# PCBv3_2_1_Arduino.net
KiCad netlist of a schematic drawn in EAGLE
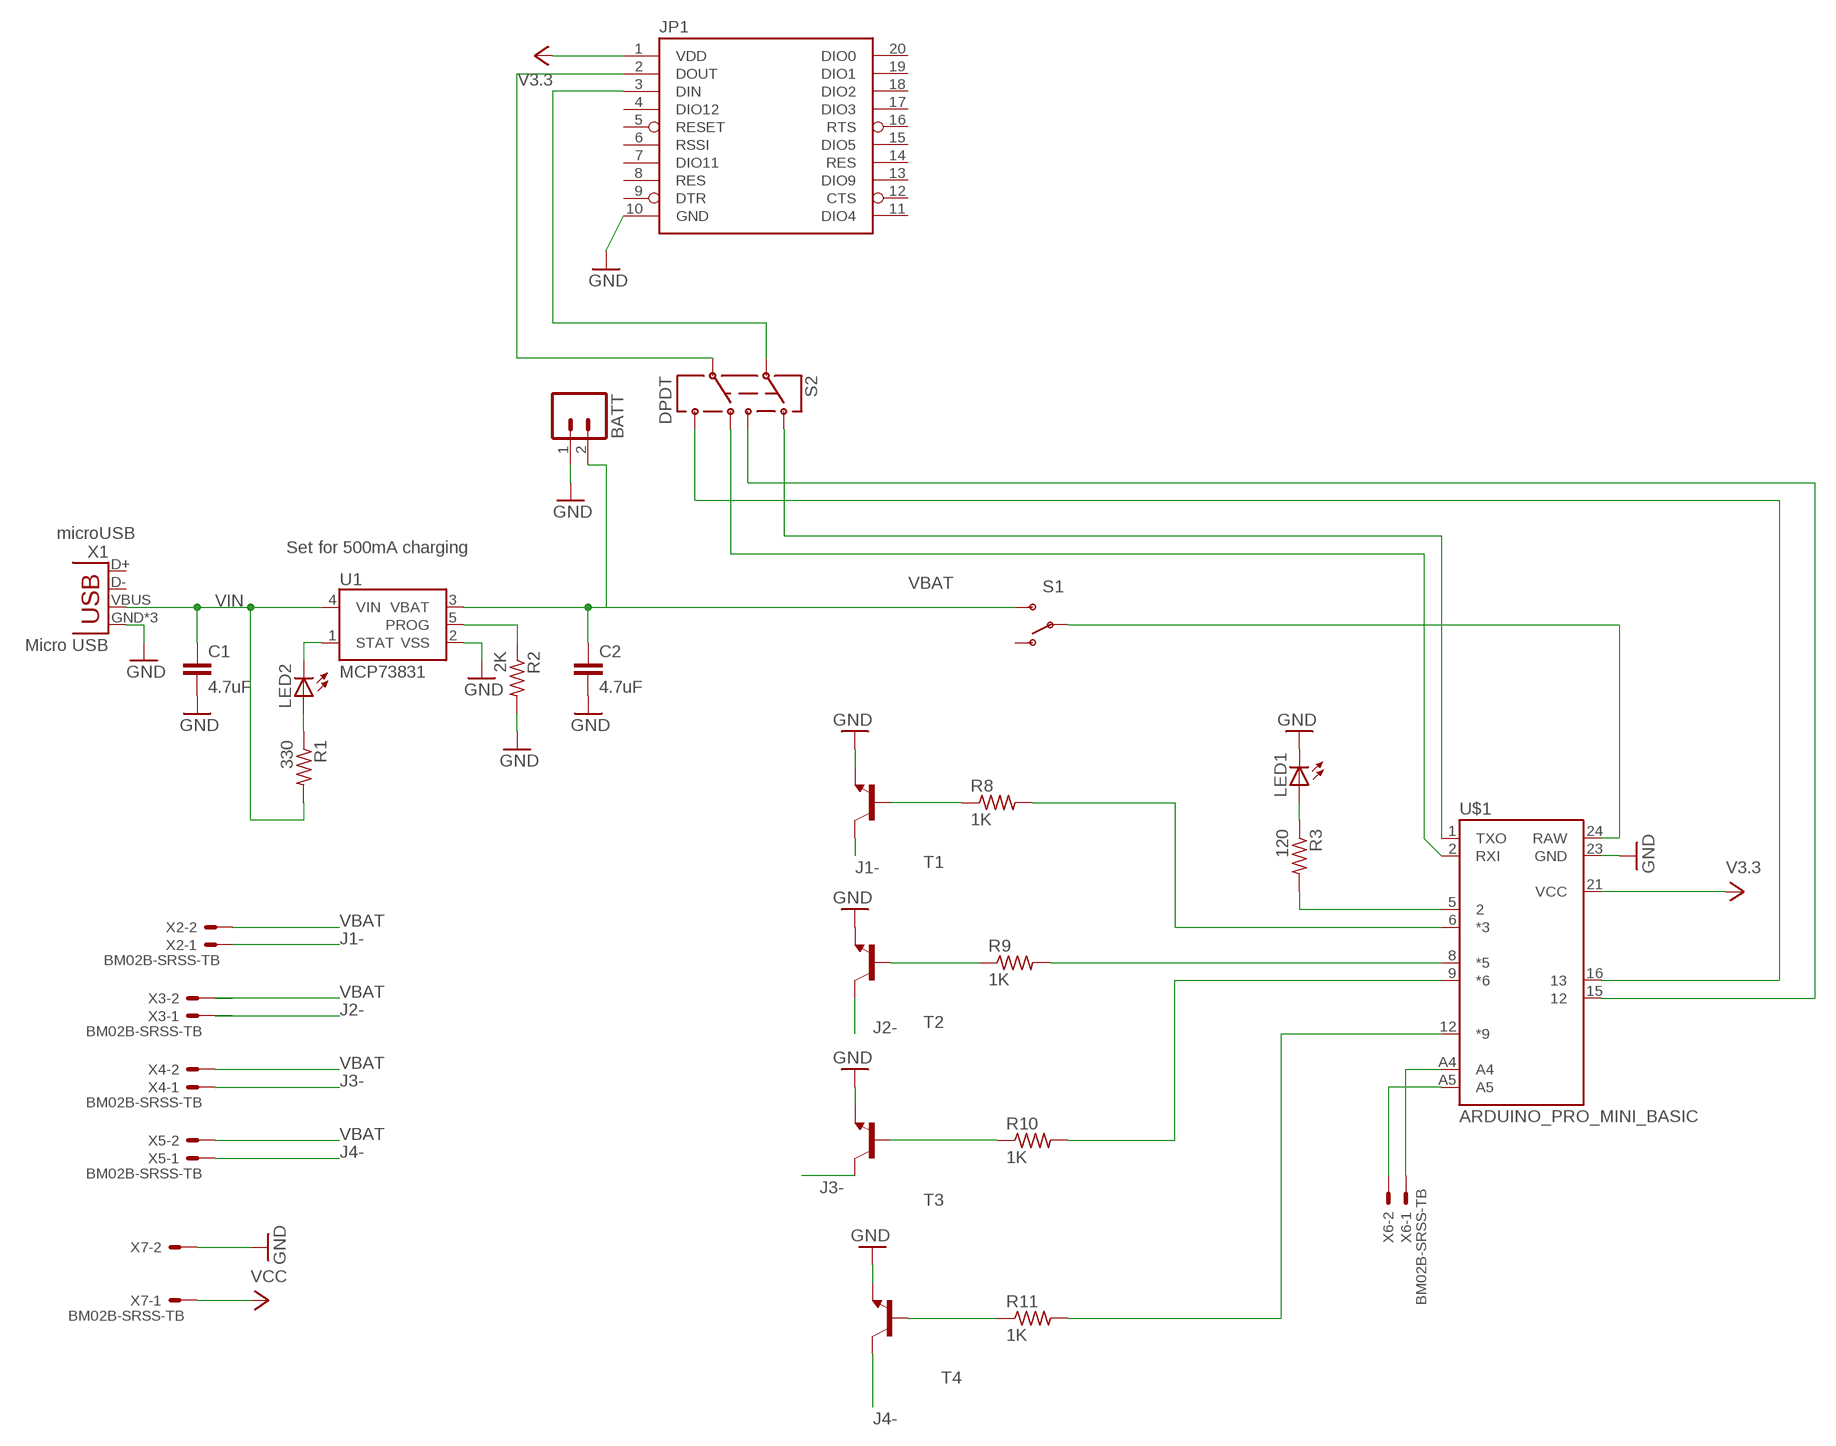
[diagram p0: schematic, sheet 1]

(export (version "E")
  (design (tool "Eeschema 10.0.6"))
  (components
    (comp (ref "BATT")
      (value "M02JST-PTH-VERT")
      (footprint "eagle-import:JST-2-PTH-VERT")
      (fields
        (field (name "MF") "JST (JAPAN SOLDERLESS TERMINALS)")
        (field (name "MPN") "S2B-PH-K-S (LF)(SN)")
      )
      (libsource (lib "eagle-import") (part "M02JST-PTH-VERT"))
    )
    (comp (ref "C1")
      (value "4.7uF")
      (footprint "eagle-import:C0805")
      (fields (field (name "MF") "TDK") (field (name "MPN") "C1005X5R0J475K050BC"))
      (libsource (lib "eagle-import") (part "C-EUC0805"))
    )
    (comp (ref "C2")
      (value "4.7uF")
      (footprint "eagle-import:C0805")
      (fields (field (name "MF") "TDK") (field (name "MPN") "C1005X5R0J475K050BC"))
      (libsource (lib "eagle-import") (part "C-EUC0805"))
    )
    (comp (ref "JP1")
      (value "XBEE-1LONGPAD")
      (footprint "eagle-import:XBEE-LONGPAD")
      (libsource (lib "eagle-import") (part "XBEE-1LONGPAD"))
    )
    (comp (ref "LED1")
      (value "LED3MM")
      (footprint "eagle-import:LED3MM")
      (fields (field (name "MF") "MULTICOMP") (field (name "MPN") "MCL034GT"))
      (libsource (lib "eagle-import") (part "LED3MM"))
    )
    (comp (ref "LED2")
      (value "LEDCHIP-LED0805")
      (footprint "eagle-import:CHIP-LED0805")
      (fields (field (name "MF") "KINGBRIGHT") (field (name "MPN") "KPT-2012QBC-D"))
      (libsource (lib "eagle-import") (part "led_LEDCHIP-LED0805"))
    )
    (comp (ref "R1")
      (value "330")
      (footprint "eagle-import:R0805")
      (fields (field (name "MF") "MULTICOMP") (field (name "MPN") "MC01W08051330R"))
      (libsource (lib "eagle-import") (part "R-US_R0805"))
    )
    (comp (ref "R2")
      (value "2K")
      (footprint "eagle-import:R0805")
      (fields (field (name "MF") "MULTICOMP") (field (name "MPN") "MC01W080512K"))
      (libsource (lib "eagle-import") (part "R-US_R0805"))
    )
    (comp (ref "R3")
      (value "120")
      (footprint "eagle-import:R0805")
      (fields (field (name "MF") "AVAGO TECHNOLOGIES") (field (name "MPN") "ASMT-YWB1-NGJB2"))
      (libsource (lib "eagle-import") (part "R-US_R0805"))
    )
    (comp (ref "R8")
      (value "1K")
      (footprint "eagle-import:R0805")
      (fields (field (name "MF") "MULTICOMP") (field (name "MPN") "MC01W08051330R"))
      (libsource (lib "eagle-import") (part "R-US_R0805"))
    )
    (comp (ref "R9")
      (value "1K")
      (footprint "eagle-import:R0805")
      (fields (field (name "MF") "MULTICOMP") (field (name "MPN") "MC01W08051330R"))
      (libsource (lib "eagle-import") (part "R-US_R0805"))
    )
    (comp (ref "R10")
      (value "1K")
      (footprint "eagle-import:R0805")
      (fields (field (name "MF") "MULTICOMP") (field (name "MPN") "MC01W08051330R"))
      (libsource (lib "eagle-import") (part "R-US_R0805"))
    )
    (comp (ref "R11")
      (value "1K")
      (footprint "eagle-import:R0805")
      (fields (field (name "MF") "MULTICOMP") (field (name "MPN") "MC01W08051330R"))
      (libsource (lib "eagle-import") (part "R-US_R0805"))
    )
    (comp (ref "S1")
      (value "SWITCH-SPDTPTH")
      (footprint "eagle-import:SWITCH-SPDT")
      (fields (field (name "MF") "EAO") (field (name "MPN") "09-10201-02"))
      (libsource (lib "eagle-import") (part "SWITCH-SPDTPTH"))
    )
    (comp (ref "S2")
      (value "DPDT")
      (footprint "eagle-import:AYZ0202")
      (fields (field (name "MF") "C & K COMPONENTS") (field (name "MPN") "AYZ0202AGRLC"))
      (libsource (lib "eagle-import") (part "AYZ0202"))
    )
    (comp (ref "T1")
      (value "BC817-16-NPN-SOT23-BEC")
      (footprint "eagle-import:SOT23-BEC")
      (fields (field (name "MF") "ON SEMICONDUCTOR") (field (name "MPN") "BC817-40LT3G"))
      (libsource (lib "eagle-import") (part "-NPN-SOT23-BECBC817-16"))
    )
    (comp (ref "T2")
      (value "BC817-16-NPN-SOT23-BEC")
      (footprint "eagle-import:SOT23-BEC")
      (fields (field (name "MF") "ON SEMICONDUCTOR") (field (name "MPN") "BC817-40LT3G"))
      (libsource (lib "eagle-import") (part "-NPN-SOT23-BECBC817-16"))
    )
    (comp (ref "T3")
      (value "BC817-16-NPN-SOT23-BEC")
      (footprint "eagle-import:SOT23-BEC")
      (fields (field (name "MF") "ON SEMICONDUCTOR") (field (name "MPN") "BC817-40LT3G"))
      (libsource (lib "eagle-import") (part "-NPN-SOT23-BECBC817-16"))
    )
    (comp (ref "T4")
      (value "BC817-16-NPN-SOT23-BEC")
      (footprint "eagle-import:SOT23-BEC")
      (fields (field (name "MF") "ON SEMICONDUCTOR") (field (name "MPN") "BC817-40LT3G"))
      (libsource (lib "eagle-import") (part "-NPN-SOT23-BECBC817-16"))
    )
    (comp (ref "U$1")
      (value "ARDUINO_PRO_MINI_BASIC")
      (footprint "eagle-import:ARDUINO_PRO_MINI_BASIC")
      (libsource (lib "eagle-import") (part "ARDUINO_PRO_MINI_BASIC"))
    )
    (comp (ref "U1")
      (value "MCP73831")
      (footprint "eagle-import:SOT23-5")
      (fields (field (name "MF") "MICROCHIP") (field (name "MPN") "MCP73831T-2ACI/OT"))
      (libsource (lib "eagle-import") (part "MCP73831"))
    )
    (comp (ref "X1")
      (value "Micro USB")
      (footprint "eagle-import:USB-MICROB")
      (fields (field (name "MF") "HIROSE(HRS)") (field (name "MPN") "ZX62-B-5PA(33)"))
      (libsource (lib "eagle-import") (part "USB-MICROB"))
    )
    (comp (ref "X2")
      (value "BM02B-SRSS-TB")
      (footprint "eagle-import:BM02B-SRSS-TB")
      (libsource (lib "eagle-import") (part "?M02B-SRSS-TBB"))
    )
    (comp (ref "X3")
      (value "BM02B-SRSS-TB")
      (footprint "eagle-import:BM02B-SRSS-TB")
      (libsource (lib "eagle-import") (part "?M02B-SRSS-TBB"))
    )
    (comp (ref "X4")
      (value "BM02B-SRSS-TB")
      (footprint "eagle-import:BM02B-SRSS-TB")
      (libsource (lib "eagle-import") (part "?M02B-SRSS-TBB"))
    )
    (comp (ref "X5")
      (value "BM02B-SRSS-TB")
      (footprint "eagle-import:BM02B-SRSS-TB")
      (libsource (lib "eagle-import") (part "?M02B-SRSS-TBB"))
    )
    (comp (ref "X6")
      (value "BM02B-SRSS-TB")
      (footprint "eagle-import:BM02B-SRSS-TB")
      (libsource (lib "eagle-import") (part "?M02B-SRSS-TBB"))
    )
    (comp (ref "X7")
      (value "BM02B-SRSS-TB")
      (footprint "eagle-import:BM02B-SRSS-TB")
      (libsource (lib "eagle-import") (part "?M02B-SRSS-TBB"))
    )
  )
  (nets
    (net (code "1") (name "/J1-") (class "Default")
      (node (ref "T1") (pin "C") (pinfunction "C_C") (pintype "passive"))
      (node (ref "X2") (pin "1") (pinfunction "S_1") (pintype "passive"))
    )
    (net (code "2") (name "/J2-") (class "Default")
      (node (ref "T2") (pin "C") (pinfunction "C_C") (pintype "passive"))
      (node (ref "X3") (pin "1") (pinfunction "S_1") (pintype "passive"))
    )
    (net (code "3") (name "/J3-") (class "Default")
      (node (ref "T3") (pin "C") (pinfunction "C_C") (pintype "passive"))
      (node (ref "X4") (pin "1") (pinfunction "S_1") (pintype "passive"))
    )
    (net (code "4") (name "/J4-") (class "Default")
      (node (ref "T4") (pin "C") (pinfunction "C_C") (pintype "passive"))
      (node (ref "X5") (pin "1") (pinfunction "S_1") (pintype "passive"))
    )
    (net (code "5") (name "/VBAT") (class "Default")
      (node (ref "BATT") (pin "2") (pinfunction "2_2") (pintype "passive"))
      (node (ref "C2") (pin "1") (pinfunction "1_1") (pintype "passive"))
      (node (ref "S1") (pin "3") (pinfunction "S_3") (pintype "passive"))
      (node (ref "U1") (pin "3") (pinfunction "VBAT_3") (pintype "power_in"))
      (node (ref "X2") (pin "2") (pinfunction "S_2") (pintype "passive"))
      (node (ref "X3") (pin "2") (pinfunction "S_2") (pintype "passive"))
      (node (ref "X4") (pin "2") (pinfunction "S_2") (pintype "passive"))
      (node (ref "X5") (pin "2") (pinfunction "S_2") (pintype "passive"))
    )
    (net (code "6") (name "/VIN") (class "Default")
      (node (ref "C1") (pin "1") (pinfunction "1_1") (pintype "passive"))
      (node (ref "R1") (pin "2") (pinfunction "2_2") (pintype "passive"))
      (node (ref "U1") (pin "4") (pinfunction "VIN_4") (pintype "power_in"))
      (node (ref "X1") (pin "VBUS") (pinfunction "VBUS_VBUS") (pintype "bidirectional"))
    )
    (net (code "7") (name "GND") (class "Default")
      (node (ref "BATT") (pin "1") (pinfunction "1_1") (pintype "passive"))
      (node (ref "C1") (pin "2") (pinfunction "2_2") (pintype "passive"))
      (node (ref "C2") (pin "2") (pinfunction "2_2") (pintype "passive"))
      (node (ref "JP1") (pin "10") (pinfunction "GND_10") (pintype "power_in"))
      (node (ref "LED1") (pin "K") (pinfunction "C_K") (pintype "passive"))
      (node (ref "R2") (pin "2") (pinfunction "2_2") (pintype "passive"))
      (node (ref "T1") (pin "E") (pinfunction "E_E") (pintype "passive"))
      (node (ref "T2") (pin "E") (pinfunction "E_E") (pintype "passive"))
      (node (ref "T3") (pin "E") (pinfunction "E_E") (pintype "passive"))
      (node (ref "T4") (pin "E") (pinfunction "E_E") (pintype "passive"))
      (node (ref "U$1") (pin "23") (pinfunction "GND_23") (pintype "bidirectional"))
      (node (ref "U1") (pin "2") (pinfunction "VSS_2") (pintype "power_in"))
      (node (ref "X1") (pin "GND") (pinfunction "GND_GND") (pintype "bidirectional"))
      (node (ref "X1") (pin "MT1") (pinfunction "GND_MT1") (pintype "bidirectional"))
      (node (ref "X1") (pin "MT2") (pinfunction "GND_MT2") (pintype "bidirectional"))
      (node (ref "X7") (pin "2") (pinfunction "S_2") (pintype "passive"))
    )
    (net (code "8") (name "Net-(JP1-DIN)") (class "Default")
      (node (ref "JP1") (pin "3") (pinfunction "DIN_3") (pintype "input"))
      (node (ref "S2") (pin "2") (pinfunction "2_2") (pintype "bidirectional"))
    )
    (net (code "9") (name "Net-(JP1-DOUT)") (class "Default")
      (node (ref "JP1") (pin "2") (pinfunction "DOUT_2") (pintype "output"))
      (node (ref "S2") (pin "5") (pinfunction "5_5") (pintype "bidirectional"))
    )
    (net (code "10") (name "Net-(LED1-PadA)") (class "Default")
      (node (ref "LED1") (pin "A") (pinfunction "A_A") (pintype "passive"))
      (node (ref "R3") (pin "1") (pinfunction "1_1") (pintype "passive"))
    )
    (net (code "11") (name "Net-(LED2-PadA)") (class "Default")
      (node (ref "LED2") (pin "A") (pinfunction "A_A") (pintype "passive"))
      (node (ref "R1") (pin "1") (pinfunction "1_1") (pintype "passive"))
    )
    (net (code "12") (name "Net-(R8-Pad1)") (class "Default")
      (node (ref "R8") (pin "1") (pinfunction "1_1") (pintype "passive"))
      (node (ref "T1") (pin "B") (pinfunction "B_B") (pintype "passive"))
    )
    (net (code "13") (name "Net-(R9-Pad1)") (class "Default")
      (node (ref "R9") (pin "1") (pinfunction "1_1") (pintype "passive"))
      (node (ref "T2") (pin "B") (pinfunction "B_B") (pintype "passive"))
    )
    (net (code "14") (name "Net-(R10-Pad1)") (class "Default")
      (node (ref "R10") (pin "1") (pinfunction "1_1") (pintype "passive"))
      (node (ref "T3") (pin "B") (pinfunction "B_B") (pintype "passive"))
    )
    (net (code "15") (name "Net-(R11-Pad1)") (class "Default")
      (node (ref "R11") (pin "1") (pinfunction "1_1") (pintype "passive"))
      (node (ref "T4") (pin "B") (pinfunction "B_B") (pintype "passive"))
    )
    (net (code "16") (name "Net-(S1-P)") (class "Default")
      (node (ref "S1") (pin "2") (pinfunction "P_2") (pintype "passive"))
      (node (ref "U$1") (pin "24") (pinfunction "RAW_24") (pintype "bidirectional"))
    )
    (net (code "17") (name "Net-(S2-1)") (class "Default")
      (node (ref "S2") (pin "3") (pinfunction "1_3") (pintype "bidirectional"))
      (node (ref "U$1") (pin "1") (pinfunction "TXO_1") (pintype "bidirectional"))
    )
    (net (code "18") (name "Net-(S2-3)") (class "Default")
      (node (ref "S2") (pin "1") (pinfunction "3_1") (pintype "bidirectional"))
      (node (ref "U$1") (pin "15") (pinfunction "12_15") (pintype "bidirectional"))
    )
    (net (code "19") (name "Net-(S2-4)") (class "Default")
      (node (ref "S2") (pin "6") (pinfunction "4_6") (pintype "bidirectional"))
      (node (ref "U$1") (pin "2") (pinfunction "RXI_2") (pintype "bidirectional"))
    )
    (net (code "20") (name "Net-(S2-6)") (class "Default")
      (node (ref "S2") (pin "4") (pinfunction "6_4") (pintype "bidirectional"))
      (node (ref "U$1") (pin "16") (pinfunction "13_16") (pintype "bidirectional"))
    )
    (net (code "21") (name "Net-(U$1-*3)") (class "Default")
      (node (ref "R8") (pin "2") (pinfunction "2_2") (pintype "passive"))
      (node (ref "U$1") (pin "6") (pinfunction "*3_6") (pintype "bidirectional"))
    )
    (net (code "22") (name "Net-(U$1-*5)") (class "Default")
      (node (ref "R9") (pin "2") (pinfunction "2_2") (pintype "passive"))
      (node (ref "U$1") (pin "8") (pinfunction "*5_8") (pintype "bidirectional"))
    )
    (net (code "23") (name "Net-(U$1-*6)") (class "Default")
      (node (ref "R10") (pin "2") (pinfunction "2_2") (pintype "passive"))
      (node (ref "U$1") (pin "9") (pinfunction "*6_9") (pintype "bidirectional"))
    )
    (net (code "24") (name "Net-(U$1-*9)") (class "Default")
      (node (ref "R11") (pin "2") (pinfunction "2_2") (pintype "passive"))
      (node (ref "U$1") (pin "12") (pinfunction "*9_12") (pintype "bidirectional"))
    )
    (net (code "25") (name "Net-(U$1-2)") (class "Default")
      (node (ref "R3") (pin "2") (pinfunction "2_2") (pintype "passive"))
      (node (ref "U$1") (pin "5") (pinfunction "2_5") (pintype "bidirectional"))
    )
    (net (code "26") (name "Net-(U1-PROG)") (class "Default")
      (node (ref "R2") (pin "1") (pinfunction "1_1") (pintype "passive"))
      (node (ref "U1") (pin "5") (pinfunction "PROG_5") (pintype "input"))
    )
    (net (code "27") (name "Net-(U1-STAT)") (class "Default")
      (node (ref "LED2") (pin "C") (pinfunction "C_C") (pintype "passive"))
      (node (ref "U1") (pin "1") (pinfunction "STAT_1") (pintype "output"))
    )
    (net (code "28") (name "Net-(X6A-S)") (class "Default")
      (node (ref "U$1") (pin "A4") (pinfunction "A4_A4") (pintype "bidirectional"))
      (node (ref "X6") (pin "1") (pinfunction "S_1") (pintype "passive"))
    )
    (net (code "29") (name "Net-(X6B-S)") (class "Default")
      (node (ref "U$1") (pin "A5") (pinfunction "A5_A5") (pintype "bidirectional"))
      (node (ref "X6") (pin "2") (pinfunction "S_2") (pintype "passive"))
    )
    (net (code "30") (name "V3.3") (class "Default")
      (node (ref "JP1") (pin "1") (pinfunction "VDD_1") (pintype "power_in"))
      (node (ref "U$1") (pin "21") (pinfunction "VCC_21") (pintype "bidirectional"))
      (node (ref "X7") (pin "1") (pinfunction "S_1") (pintype "passive"))
    )
    (net (code "31") (name "unconnected-(JP1-CTS-Pad12)") (class "Default")
      (node (ref "JP1") (pin "12") (pinfunction "CTS_12") (pintype "output"))
    )
    (net (code "32") (name "unconnected-(JP1-DIO0-Pad20)") (class "Default")
      (node (ref "JP1") (pin "20") (pinfunction "DIO0_20") (pintype "bidirectional"))
    )
    (net (code "33") (name "unconnected-(JP1-DIO1-Pad19)") (class "Default")
      (node (ref "JP1") (pin "19") (pinfunction "DIO1_19") (pintype "bidirectional"))
    )
    (net (code "34") (name "unconnected-(JP1-DIO2-Pad18)") (class "Default")
      (node (ref "JP1") (pin "18") (pinfunction "DIO2_18") (pintype "bidirectional"))
    )
    (net (code "35") (name "unconnected-(JP1-DIO3-Pad17)") (class "Default")
      (node (ref "JP1") (pin "17") (pinfunction "DIO3_17") (pintype "bidirectional"))
    )
    (net (code "36") (name "unconnected-(JP1-DIO4-Pad11)") (class "Default")
      (node (ref "JP1") (pin "11") (pinfunction "DIO4_11") (pintype "bidirectional"))
    )
    (net (code "37") (name "unconnected-(JP1-DIO5-Pad15)") (class "Default")
      (node (ref "JP1") (pin "15") (pinfunction "DIO5_15") (pintype "bidirectional"))
    )
    (net (code "38") (name "unconnected-(JP1-DIO9-Pad13)") (class "Default")
      (node (ref "JP1") (pin "13") (pinfunction "DIO9_13") (pintype "bidirectional"))
    )
    (net (code "39") (name "unconnected-(JP1-DIO11-Pad7)") (class "Default")
      (node (ref "JP1") (pin "7") (pinfunction "DIO11_7") (pintype "bidirectional"))
    )
    (net (code "40") (name "unconnected-(JP1-DIO12-Pad4)") (class "Default")
      (node (ref "JP1") (pin "4") (pinfunction "DIO12_4") (pintype "bidirectional"))
    )
    (net (code "41") (name "unconnected-(JP1-DTR-Pad9)") (class "Default")
      (node (ref "JP1") (pin "9") (pinfunction "DTR_9") (pintype "bidirectional"))
    )
    (net (code "42") (name "unconnected-(JP1-RES-Pad8)") (class "Default")
      (node (ref "JP1") (pin "8") (pinfunction "RES_8") (pintype "bidirectional"))
    )
    (net (code "43") (name "unconnected-(JP1-RES-Pad14)") (class "Default")
      (node (ref "JP1") (pin "14") (pinfunction "RES_14") (pintype "bidirectional"))
    )
    (net (code "44") (name "unconnected-(JP1-RESET-Pad5)") (class "Default")
      (node (ref "JP1") (pin "5") (pinfunction "RESET_5") (pintype "input"))
    )
    (net (code "45") (name "unconnected-(JP1-RSSI-Pad6)") (class "Default")
      (node (ref "JP1") (pin "6") (pinfunction "RSSI_6") (pintype "bidirectional"))
    )
    (net (code "46") (name "unconnected-(JP1-RTS-Pad16)") (class "Default")
      (node (ref "JP1") (pin "16") (pinfunction "RTS_16") (pintype "input"))
    )
    (net (code "47") (name "unconnected-(S1-O-Pad1)") (class "Default")
      (node (ref "S1") (pin "1") (pinfunction "O_1") (pintype "passive"))
    )
    (net (code "48") (name "unconnected-(X1-PadD+)") (class "Default")
      (node (ref "X1") (pin "D+") (pinfunction "D+_D+") (pintype "bidirectional"))
    )
    (net (code "49") (name "unconnected-(X1-PadD-)") (class "Default")
      (node (ref "X1") (pin "D-") (pinfunction "D-_D-") (pintype "bidirectional"))
    )
  )
)
